# GR_Split.net
KiCad netlist of a schematic drawn in Altium Designer
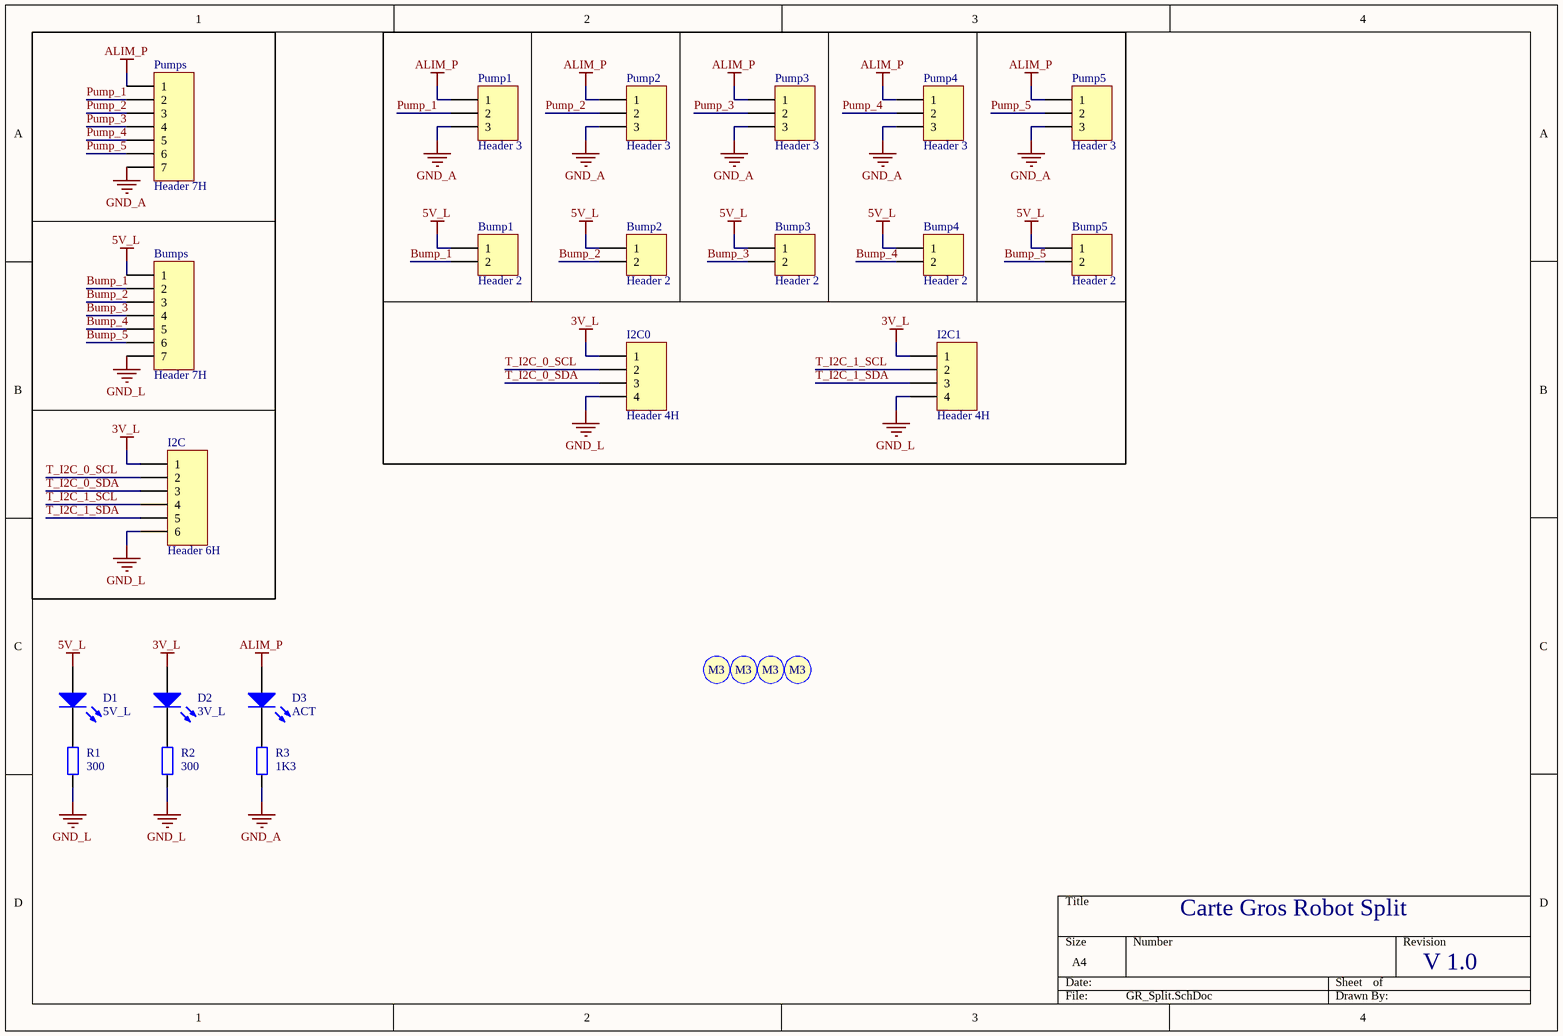
[diagram p0: GR_Split.SchDoc]

(export (version "E")
  (design (tool "Eeschema 10.0.6"))
  (components
    (comp (ref "Bump1")
      (value "Header 2")
      (footprint "B2B-XH-A")
      (description "Header, 2-Pin")
      (fields (field (name "PUBLISHER") "Altium Limited"))
      (libsource (lib "Miscellaneous Connectors") (part "Header 2"))
    )
    (comp (ref "Bump2")
      (value "Header 2")
      (footprint "B2B-XH-A")
      (description "Header, 2-Pin")
      (fields (field (name "PUBLISHER") "Altium Limited"))
      (libsource (lib "Miscellaneous Connectors") (part "Header 2"))
    )
    (comp (ref "Bump3")
      (value "Header 2")
      (footprint "B2B-XH-A")
      (description "Header, 2-Pin")
      (fields (field (name "PUBLISHER") "Altium Limited"))
      (libsource (lib "Miscellaneous Connectors") (part "Header 2"))
    )
    (comp (ref "Bump4")
      (value "Header 2")
      (footprint "B2B-XH-A")
      (description "Header, 2-Pin")
      (fields (field (name "PUBLISHER") "Altium Limited"))
      (libsource (lib "Miscellaneous Connectors") (part "Header 2"))
    )
    (comp (ref "Bump5")
      (value "Header 2")
      (footprint "B2B-XH-A")
      (description "Header, 2-Pin")
      (fields (field (name "PUBLISHER") "Altium Limited"))
      (libsource (lib "Miscellaneous Connectors") (part "Header 2"))
    )
    (comp (ref "Bumps")
      (value "Header 7H")
      (footprint "B7B-XH-A")
      (description "Header, 7-Pin, Right Angle")
      (fields (field (name "PUBLISHER") "Altium Limited"))
      (libsource (lib "Miscellaneous Connectors") (part "Header 7H"))
    )
    (comp (ref "D1")
      (value "5V_L")
      (footprint "KP-3216SEC")
      (description "Typical RED, GREEN, YELLOW, AMBER GaAs LED")
      (fields (field (name "PUBLISHER") "Altium Limited"))
      (libsource (lib "Miscellaneous Devices") (part "LED2"))
    )
    (comp (ref "D2")
      (value "3V_L")
      (footprint "KP-3216SEC")
      (description "Typical RED, GREEN, YELLOW, AMBER GaAs LED")
      (fields (field (name "PUBLISHER") "Altium Limited"))
      (libsource (lib "Miscellaneous Devices") (part "LED2"))
    )
    (comp (ref "D3")
      (value "ACT")
      (footprint "KP-3216SEC")
      (description "Typical RED, GREEN, YELLOW, AMBER GaAs LED")
      (fields (field (name "PUBLISHER") "Altium Limited"))
      (libsource (lib "Miscellaneous Devices") (part "LED2"))
    )
    (comp (ref "I2C")
      (value "Header 6H")
      (footprint "B6B-XH-A")
      (description "Header, 6-Pin, Right Angle")
      (fields (field (name "PUBLISHER") "Altium Limited"))
      (libsource (lib "Miscellaneous Connectors") (part "Header 6H"))
    )
    (comp (ref "I2C0")
      (value "Header 4H")
      (footprint "B4B-XH-A")
      (description "Header, 4-Pin, Right Angle")
      (fields (field (name "PUBLISHER") "Altium Limited"))
      (libsource (lib "Miscellaneous Connectors") (part "Header 4H"))
    )
    (comp (ref "I2C1")
      (value "Header 4H")
      (footprint "B4B-XH-A")
      (description "Header, 4-Pin, Right Angle")
      (fields (field (name "PUBLISHER") "Altium Limited"))
      (libsource (lib "Miscellaneous Connectors") (part "Header 4H"))
    )
    (comp (ref "Pump1")
      (value "Header 3")
      (footprint "B3B-XH-A")
      (description "Header, 3-Pin")
      (fields (field (name "PUBLISHER") "Altium Limited"))
      (libsource (lib "Miscellaneous Connectors") (part "Header 3"))
    )
    (comp (ref "Pump2")
      (value "Header 3")
      (footprint "B3B-XH-A")
      (description "Header, 3-Pin")
      (fields (field (name "PUBLISHER") "Altium Limited"))
      (libsource (lib "Miscellaneous Connectors") (part "Header 3"))
    )
    (comp (ref "Pump3")
      (value "Header 3")
      (footprint "B3B-XH-A")
      (description "Header, 3-Pin")
      (fields (field (name "PUBLISHER") "Altium Limited"))
      (libsource (lib "Miscellaneous Connectors") (part "Header 3"))
    )
    (comp (ref "Pump4")
      (value "Header 3")
      (footprint "B3B-XH-A")
      (description "Header, 3-Pin")
      (fields (field (name "PUBLISHER") "Altium Limited"))
      (libsource (lib "Miscellaneous Connectors") (part "Header 3"))
    )
    (comp (ref "Pump5")
      (value "Header 3")
      (footprint "B3B-XH-A")
      (description "Header, 3-Pin")
      (fields (field (name "PUBLISHER") "Altium Limited"))
      (libsource (lib "Miscellaneous Connectors") (part "Header 3"))
    )
    (comp (ref "Pumps")
      (value "Header 7H")
      (footprint "B7B-XH-A")
      (description "Header, 7-Pin, Right Angle")
      (fields (field (name "PUBLISHER") "Altium Limited"))
      (libsource (lib "Miscellaneous Connectors") (part "Header 7H"))
    )
    (comp (ref "R1")
      (value "300")
      (footprint "Resistor 1206")
      (description "Resistor")
      (fields (field (name "Comment") "Res2") (field (name "PUBLISHER") "Altium Limited"))
      (libsource (lib "Miscellaneous Devices") (part "Res2"))
    )
    (comp (ref "R2")
      (value "300")
      (footprint "Resistor 1206")
      (description "Resistor")
      (fields (field (name "Comment") "Res2") (field (name "PUBLISHER") "Altium Limited"))
      (libsource (lib "Miscellaneous Devices") (part "Res2"))
    )
    (comp (ref "R3")
      (value "1K3")
      (footprint "Resistor 1206")
      (description "Resistor")
      (fields (field (name "Comment") "Res2") (field (name "PUBLISHER") "Altium Limited"))
      (libsource (lib "") (part "Res2_1"))
    )
    (comp (ref "S1")
      (value "Screw M3")
      (footprint "Screw M3")
      (libsource (lib "SupaeroRobot") (part "Screw M3"))
    )
    (comp (ref "S2")
      (value "Screw M3")
      (footprint "Screw M3")
      (libsource (lib "SupaeroRobot") (part "Screw M3"))
    )
    (comp (ref "S3")
      (value "Screw M3")
      (footprint "Screw M3")
      (libsource (lib "SupaeroRobot") (part "Screw M3"))
    )
    (comp (ref "S4")
      (value "Screw M3")
      (footprint "Screw M3")
      (libsource (lib "SupaeroRobot") (part "Screw M3"))
    )
  )
  (nets
    (net (code "1") (name "/Bump_1") (class "Default")
      (node (ref "Bump1") (pin "2") (pinfunction "2_2") (pintype "passive"))
      (node (ref "Bumps") (pin "2") (pinfunction "2_2") (pintype "passive"))
    )
    (net (code "2") (name "/Bump_2") (class "Default")
      (node (ref "Bump2") (pin "2") (pinfunction "2_2") (pintype "passive"))
      (node (ref "Bumps") (pin "3") (pinfunction "3_3") (pintype "passive"))
    )
    (net (code "3") (name "/Bump_3") (class "Default")
      (node (ref "Bump3") (pin "2") (pinfunction "2_2") (pintype "passive"))
      (node (ref "Bumps") (pin "4") (pinfunction "4_4") (pintype "passive"))
    )
    (net (code "4") (name "/Bump_4") (class "Default")
      (node (ref "Bump4") (pin "2") (pinfunction "2_2") (pintype "passive"))
      (node (ref "Bumps") (pin "5") (pinfunction "5_5") (pintype "passive"))
    )
    (net (code "5") (name "/Bump_5") (class "Default")
      (node (ref "Bump5") (pin "2") (pinfunction "2_2") (pintype "passive"))
      (node (ref "Bumps") (pin "6") (pinfunction "6_6") (pintype "passive"))
    )
    (net (code "6") (name "/Pump_1") (class "Default")
      (node (ref "Pump1") (pin "2") (pinfunction "2_2") (pintype "passive"))
      (node (ref "Pumps") (pin "2") (pinfunction "2_2") (pintype "passive"))
    )
    (net (code "7") (name "/Pump_2") (class "Default")
      (node (ref "Pump2") (pin "2") (pinfunction "2_2") (pintype "passive"))
      (node (ref "Pumps") (pin "3") (pinfunction "3_3") (pintype "passive"))
    )
    (net (code "8") (name "/Pump_3") (class "Default")
      (node (ref "Pump3") (pin "2") (pinfunction "2_2") (pintype "passive"))
      (node (ref "Pumps") (pin "4") (pinfunction "4_4") (pintype "passive"))
    )
    (net (code "9") (name "/Pump_4") (class "Default")
      (node (ref "Pump4") (pin "2") (pinfunction "2_2") (pintype "passive"))
      (node (ref "Pumps") (pin "5") (pinfunction "5_5") (pintype "passive"))
    )
    (net (code "10") (name "/Pump_5") (class "Default")
      (node (ref "Pump5") (pin "2") (pinfunction "2_2") (pintype "passive"))
      (node (ref "Pumps") (pin "6") (pinfunction "6_6") (pintype "passive"))
    )
    (net (code "11") (name "/T_I2C_0_SCL") (class "Default")
      (node (ref "I2C") (pin "2") (pinfunction "2_2") (pintype "passive"))
      (node (ref "I2C0") (pin "2") (pinfunction "2_2") (pintype "passive"))
    )
    (net (code "12") (name "/T_I2C_0_SDA") (class "Default")
      (node (ref "I2C") (pin "3") (pinfunction "3_3") (pintype "passive"))
      (node (ref "I2C0") (pin "3") (pinfunction "3_3") (pintype "passive"))
    )
    (net (code "13") (name "/T_I2C_1_SCL") (class "Default")
      (node (ref "I2C") (pin "4") (pinfunction "4_4") (pintype "passive"))
      (node (ref "I2C1") (pin "2") (pinfunction "2_2") (pintype "passive"))
    )
    (net (code "14") (name "/T_I2C_1_SDA") (class "Default")
      (node (ref "I2C") (pin "5") (pinfunction "5_5") (pintype "passive"))
      (node (ref "I2C1") (pin "3") (pinfunction "3_3") (pintype "passive"))
    )
    (net (code "15") (name "3V_L") (class "Default")
      (node (ref "D2") (pin "1") (pinfunction "A_1") (pintype "passive"))
      (node (ref "I2C") (pin "1") (pinfunction "1_1") (pintype "passive"))
      (node (ref "I2C0") (pin "1") (pinfunction "1_1") (pintype "passive"))
      (node (ref "I2C1") (pin "1") (pinfunction "1_1") (pintype "passive"))
    )
    (net (code "16") (name "5V_L") (class "Default")
      (node (ref "Bump1") (pin "1") (pinfunction "1_1") (pintype "passive"))
      (node (ref "Bump2") (pin "1") (pinfunction "1_1") (pintype "passive"))
      (node (ref "Bump3") (pin "1") (pinfunction "1_1") (pintype "passive"))
      (node (ref "Bump4") (pin "1") (pinfunction "1_1") (pintype "passive"))
      (node (ref "Bump5") (pin "1") (pinfunction "1_1") (pintype "passive"))
      (node (ref "Bumps") (pin "1") (pinfunction "1_1") (pintype "passive"))
      (node (ref "D1") (pin "1") (pinfunction "A_1") (pintype "passive"))
    )
    (net (code "17") (name "ALIM_P") (class "Default")
      (node (ref "D3") (pin "1") (pinfunction "A_1") (pintype "passive"))
      (node (ref "Pump1") (pin "1") (pinfunction "1_1") (pintype "passive"))
      (node (ref "Pump2") (pin "1") (pinfunction "1_1") (pintype "passive"))
      (node (ref "Pump3") (pin "1") (pinfunction "1_1") (pintype "passive"))
      (node (ref "Pump4") (pin "1") (pinfunction "1_1") (pintype "passive"))
      (node (ref "Pump5") (pin "1") (pinfunction "1_1") (pintype "passive"))
      (node (ref "Pumps") (pin "1") (pinfunction "1_1") (pintype "passive"))
    )
    (net (code "18") (name "GND_A") (class "Default")
      (node (ref "Pump1") (pin "3") (pinfunction "3_3") (pintype "passive"))
      (node (ref "Pump2") (pin "3") (pinfunction "3_3") (pintype "passive"))
      (node (ref "Pump3") (pin "3") (pinfunction "3_3") (pintype "passive"))
      (node (ref "Pump4") (pin "3") (pinfunction "3_3") (pintype "passive"))
      (node (ref "Pump5") (pin "3") (pinfunction "3_3") (pintype "passive"))
      (node (ref "Pumps") (pin "7") (pinfunction "7_7") (pintype "passive"))
      (node (ref "R3") (pin "2") (pinfunction "2_2") (pintype "passive"))
    )
    (net (code "19") (name "GND_L") (class "Default")
      (node (ref "Bumps") (pin "7") (pinfunction "7_7") (pintype "passive"))
      (node (ref "I2C") (pin "6") (pinfunction "6_6") (pintype "passive"))
      (node (ref "I2C0") (pin "4") (pinfunction "4_4") (pintype "passive"))
      (node (ref "I2C1") (pin "4") (pinfunction "4_4") (pintype "passive"))
      (node (ref "R1") (pin "1") (pinfunction "1_1") (pintype "passive"))
      (node (ref "R2") (pin "1") (pinfunction "1_1") (pintype "passive"))
    )
    (net (code "20") (name "Net-(D1-K)") (class "Default")
      (node (ref "D1") (pin "2") (pinfunction "K_2") (pintype "passive"))
      (node (ref "R1") (pin "2") (pinfunction "2_2") (pintype "passive"))
    )
    (net (code "21") (name "Net-(D2-K)") (class "Default")
      (node (ref "D2") (pin "2") (pinfunction "K_2") (pintype "passive"))
      (node (ref "R2") (pin "2") (pinfunction "2_2") (pintype "passive"))
    )
    (net (code "22") (name "Net-(D3-K)") (class "Default")
      (node (ref "D3") (pin "2") (pinfunction "K_2") (pintype "passive"))
      (node (ref "R3") (pin "1") (pinfunction "1_1") (pintype "passive"))
    )
  )
)
